# BMS_AFE_-_Cell_Inputs.net
KiCad netlist of a schematic drawn in Altium Designer
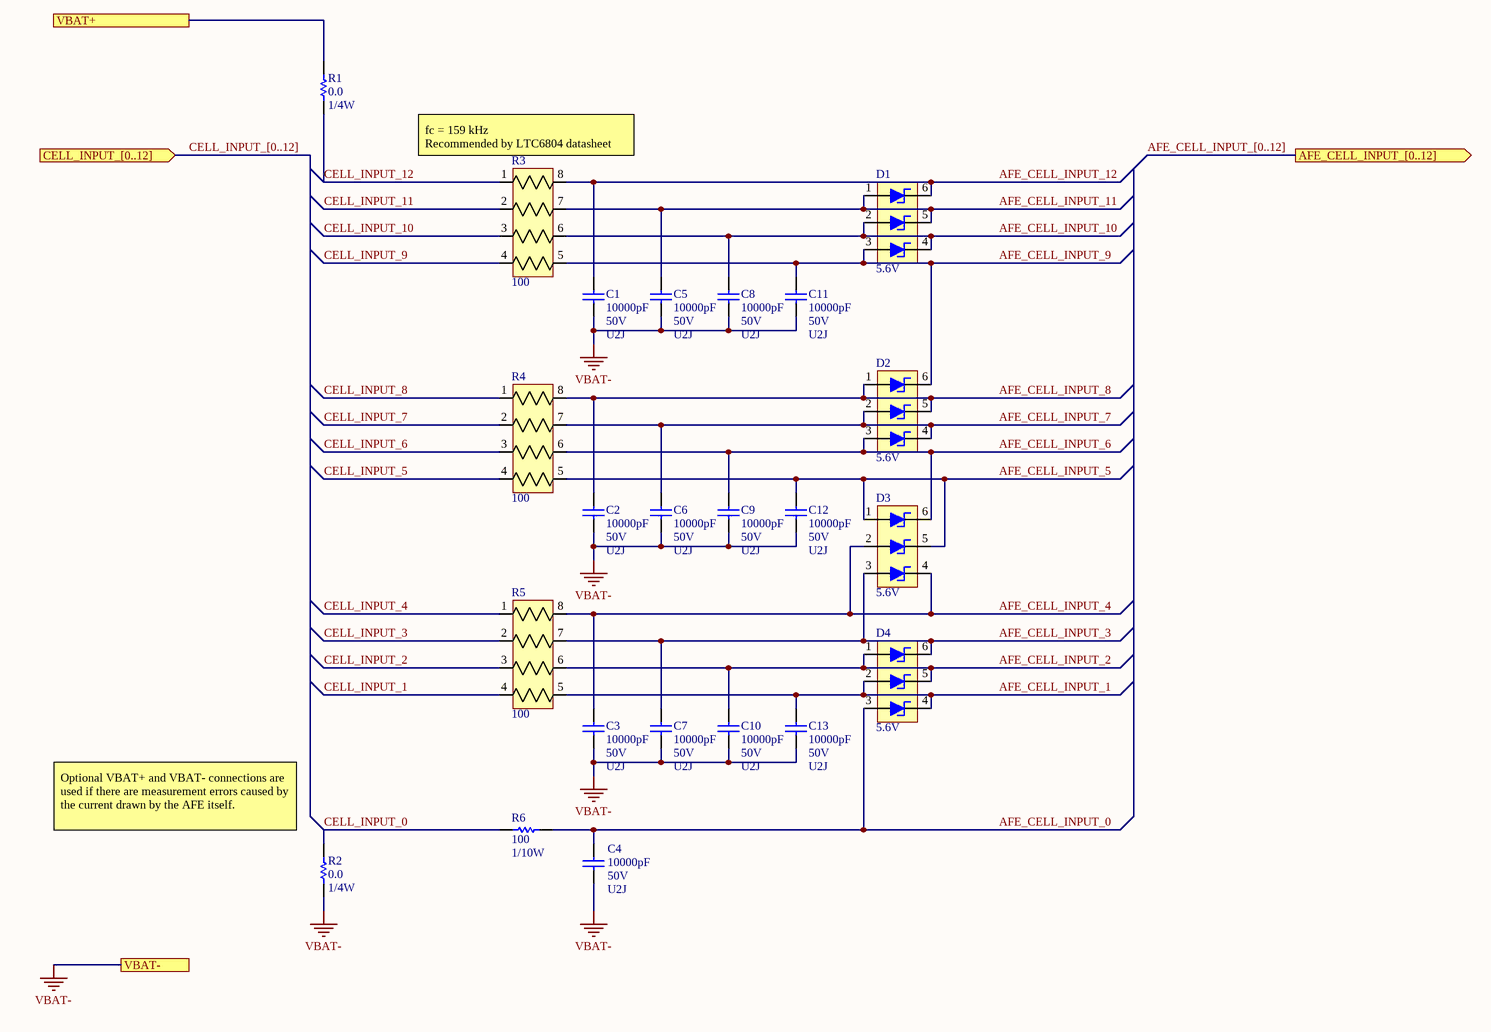
[diagram p0: BMS AFE - Cell Inputs.SchDoc]

(export (version "E")
  (design (tool "Eeschema 10.0.6"))
  (components
    (comp (ref "C1")
      (value "CAP CER 10nF 50V 5% X7R 0603")
      (footprint "CAP, 0603")
      (description "10000pF ±5% 50V Ceramic Capacitor U2J 0603 (1608 Metric)")
      (fields
        (field (name "TOLERANCE") "±5%")
        (field (name "CAPACITANCE") "10000pF")
        (field (name "VOLTAGE") "50V")
        (field (name "TEMPERATURE COEFFICIENT") "U2J")
      )
      (libsource (lib "Schematic Diagrams") (part "CAP CER 10nF 50V 5% X7R 0603"))
    )
    (comp (ref "C2")
      (value "CAP CER 10nF 50V 5% X7R 0603")
      (footprint "CAP, 0603")
      (description "10000pF ±5% 50V Ceramic Capacitor U2J 0603 (1608 Metric)")
      (fields
        (field (name "TOLERANCE") "±5%")
        (field (name "CAPACITANCE") "10000pF")
        (field (name "VOLTAGE") "50V")
        (field (name "TEMPERATURE COEFFICIENT") "U2J")
      )
      (libsource (lib "Schematic Diagrams") (part "CAP CER 10nF 50V 5% X7R 0603"))
    )
    (comp (ref "C3")
      (value "CAP CER 10nF 50V 5% X7R 0603")
      (footprint "CAP, 0603")
      (description "10000pF ±5% 50V Ceramic Capacitor U2J 0603 (1608 Metric)")
      (fields
        (field (name "TOLERANCE") "±5%")
        (field (name "CAPACITANCE") "10000pF")
        (field (name "VOLTAGE") "50V")
        (field (name "TEMPERATURE COEFFICIENT") "U2J")
      )
      (libsource (lib "Schematic Diagrams") (part "CAP CER 10nF 50V 5% X7R 0603"))
    )
    (comp (ref "C4")
      (value "CAP CER 10nF 50V 5% X7R 0603")
      (footprint "CAP, 0603")
      (description "10000pF ±5% 50V Ceramic Capacitor U2J 0603 (1608 Metric)")
      (fields
        (field (name "TOLERANCE") "±5%")
        (field (name "CAPACITANCE") "10000pF")
        (field (name "VOLTAGE") "50V")
        (field (name "TEMPERATURE COEFFICIENT") "U2J")
      )
      (libsource (lib "Schematic Diagrams") (part "CAP CER 10nF 50V 5% X7R 0603"))
    )
    (comp (ref "C5")
      (value "CAP CER 10nF 50V 5% X7R 0603")
      (footprint "CAP, 0603")
      (description "10000pF ±5% 50V Ceramic Capacitor U2J 0603 (1608 Metric)")
      (fields
        (field (name "TOLERANCE") "±5%")
        (field (name "CAPACITANCE") "10000pF")
        (field (name "VOLTAGE") "50V")
        (field (name "TEMPERATURE COEFFICIENT") "U2J")
      )
      (libsource (lib "Schematic Diagrams") (part "CAP CER 10nF 50V 5% X7R 0603"))
    )
    (comp (ref "C6")
      (value "CAP CER 10nF 50V 5% X7R 0603")
      (footprint "CAP, 0603")
      (description "10000pF ±5% 50V Ceramic Capacitor U2J 0603 (1608 Metric)")
      (fields
        (field (name "TOLERANCE") "±5%")
        (field (name "CAPACITANCE") "10000pF")
        (field (name "VOLTAGE") "50V")
        (field (name "TEMPERATURE COEFFICIENT") "U2J")
      )
      (libsource (lib "Schematic Diagrams") (part "CAP CER 10nF 50V 5% X7R 0603"))
    )
    (comp (ref "C7")
      (value "CAP CER 10nF 50V 5% X7R 0603")
      (footprint "CAP, 0603")
      (description "10000pF ±5% 50V Ceramic Capacitor U2J 0603 (1608 Metric)")
      (fields
        (field (name "TOLERANCE") "±5%")
        (field (name "CAPACITANCE") "10000pF")
        (field (name "VOLTAGE") "50V")
        (field (name "TEMPERATURE COEFFICIENT") "U2J")
      )
      (libsource (lib "Schematic Diagrams") (part "CAP CER 10nF 50V 5% X7R 0603"))
    )
    (comp (ref "C8")
      (value "CAP CER 10nF 50V 5% X7R 0603")
      (footprint "CAP, 0603")
      (description "10000pF ±5% 50V Ceramic Capacitor U2J 0603 (1608 Metric)")
      (fields
        (field (name "TOLERANCE") "±5%")
        (field (name "CAPACITANCE") "10000pF")
        (field (name "VOLTAGE") "50V")
        (field (name "TEMPERATURE COEFFICIENT") "U2J")
      )
      (libsource (lib "Schematic Diagrams") (part "CAP CER 10nF 50V 5% X7R 0603"))
    )
    (comp (ref "C9")
      (value "CAP CER 10nF 50V 5% X7R 0603")
      (footprint "CAP, 0603")
      (description "10000pF ±5% 50V Ceramic Capacitor U2J 0603 (1608 Metric)")
      (fields
        (field (name "TOLERANCE") "±5%")
        (field (name "CAPACITANCE") "10000pF")
        (field (name "VOLTAGE") "50V")
        (field (name "TEMPERATURE COEFFICIENT") "U2J")
      )
      (libsource (lib "Schematic Diagrams") (part "CAP CER 10nF 50V 5% X7R 0603"))
    )
    (comp (ref "C10")
      (value "CAP CER 10nF 50V 5% X7R 0603")
      (footprint "CAP, 0603")
      (description "10000pF ±5% 50V Ceramic Capacitor U2J 0603 (1608 Metric)")
      (fields
        (field (name "TOLERANCE") "±5%")
        (field (name "CAPACITANCE") "10000pF")
        (field (name "VOLTAGE") "50V")
        (field (name "TEMPERATURE COEFFICIENT") "U2J")
      )
      (libsource (lib "Schematic Diagrams") (part "CAP CER 10nF 50V 5% X7R 0603"))
    )
    (comp (ref "C11")
      (value "CAP CER 10nF 50V 5% X7R 0603")
      (footprint "CAP, 0603")
      (description "10000pF ±5% 50V Ceramic Capacitor U2J 0603 (1608 Metric)")
      (fields
        (field (name "TOLERANCE") "±5%")
        (field (name "CAPACITANCE") "10000pF")
        (field (name "VOLTAGE") "50V")
        (field (name "TEMPERATURE COEFFICIENT") "U2J")
      )
      (libsource (lib "Schematic Diagrams") (part "CAP CER 10nF 50V 5% X7R 0603"))
    )
    (comp (ref "C12")
      (value "CAP CER 10nF 50V 5% X7R 0603")
      (footprint "CAP, 0603")
      (description "10000pF ±5% 50V Ceramic Capacitor U2J 0603 (1608 Metric)")
      (fields
        (field (name "TOLERANCE") "±5%")
        (field (name "CAPACITANCE") "10000pF")
        (field (name "VOLTAGE") "50V")
        (field (name "TEMPERATURE COEFFICIENT") "U2J")
      )
      (libsource (lib "Schematic Diagrams") (part "CAP CER 10nF 50V 5% X7R 0603"))
    )
    (comp (ref "C13")
      (value "CAP CER 10nF 50V 5% X7R 0603")
      (footprint "CAP, 0603")
      (description "10000pF ±5% 50V Ceramic Capacitor U2J 0603 (1608 Metric)")
      (fields
        (field (name "TOLERANCE") "±5%")
        (field (name "CAPACITANCE") "10000pF")
        (field (name "VOLTAGE") "50V")
        (field (name "TEMPERATURE COEFFICIENT") "U2J")
      )
      (libsource (lib "Schematic Diagrams") (part "CAP CER 10nF 50V 5% X7R 0603"))
    )
    (comp (ref "D1")
      (value "5.6V")
      (footprint "SOT-363")
      (description "Zener Diode Array 3 Independent 5.6V 200mW ±6% SOT-363")
      (fields (field (name "TOLERANCE") "6%") (field (name "MANUFACTURER") "Diodes"))
      (libsource (lib "Schematic Diagrams") (part "DIODE ZENER ARRAY 5.6V SOT363"))
    )
    (comp (ref "D2")
      (value "5.6V")
      (footprint "SOT-363")
      (description "Zener Diode Array 3 Independent 5.6V 200mW ±6% SOT-363")
      (fields (field (name "TOLERANCE") "6%") (field (name "MANUFACTURER") "Diodes"))
      (libsource (lib "Schematic Diagrams") (part "DIODE ZENER ARRAY 5.6V SOT363"))
    )
    (comp (ref "D3")
      (value "5.6V")
      (footprint "SOT-363")
      (description "Zener Diode Array 3 Independent 5.6V 200mW ±6% SOT-363")
      (fields (field (name "TOLERANCE") "6%") (field (name "MANUFACTURER") "Diodes"))
      (libsource (lib "Schematic Diagrams") (part "DIODE ZENER ARRAY 5.6V SOT363"))
    )
    (comp (ref "D4")
      (value "5.6V")
      (footprint "SOT-363")
      (description "Zener Diode Array 3 Independent 5.6V 200mW ±6% SOT-363")
      (fields (field (name "TOLERANCE") "6%") (field (name "MANUFACTURER") "Diodes"))
      (libsource (lib "Schematic Diagrams") (part "DIODE ZENER ARRAY 5.6V SOT363"))
    )
    (comp (ref "R1")
      (value "RES 0.0 OHM 1/4W 0603")
      (footprint "RES, 0603")
      (description "RES SMD 0.0 OHM JUMPER 1/4W 0603")
      (fields (field (name "RESISTANCE") "0.0") (field (name "POWER (WATTS)") "1/4W"))
      (libsource (lib "Schematic Diagrams") (part "RES 0.0 OHM 1/4W 0603"))
    )
    (comp (ref "R2")
      (value "RES 0.0 OHM 1/4W 0603")
      (footprint "RES, 0603")
      (description "RES SMD 0.0 OHM JUMPER 1/4W 0603")
      (fields (field (name "RESISTANCE") "0.0") (field (name "POWER (WATTS)") "1/4W"))
      (libsource (lib "Schematic Diagrams") (part "RES 0.0 OHM 1/4W 0603"))
    )
    (comp (ref "R3")
      (value "RES ARRAY 100 OHM 0.5% 4RES 1206")
      (footprint "RES ARRAY 4RES 1206")
      (fields
        (field (name "MANUFACTURER") "Vishay Beyschlag")
        (field (name "MANUFACTURER PART NUMBER") "ACASA1002S1002P100")
        (field (name "TOLERANCE") "±0.5%")
        (field (name "RESISTANCE") "100")
      )
      (libsource (lib "Schematic Diagrams") (part "RES ARRAY 100 OHM 0.5% 4RES 1206"))
    )
    (comp (ref "R4")
      (value "RES ARRAY 100 OHM 0.5% 4RES 1206")
      (footprint "RES ARRAY 4RES 1206")
      (fields
        (field (name "MANUFACTURER") "Vishay Beyschlag")
        (field (name "MANUFACTURER PART NUMBER") "ACASA1002S1002P100")
        (field (name "TOLERANCE") "±0.5%")
        (field (name "RESISTANCE") "100")
      )
      (libsource (lib "Schematic Diagrams") (part "RES ARRAY 100 OHM 0.5% 4RES 1206"))
    )
    (comp (ref "R5")
      (value "RES ARRAY 100 OHM 0.5% 4RES 1206")
      (footprint "RES ARRAY 4RES 1206")
      (fields
        (field (name "MANUFACTURER") "Vishay Beyschlag")
        (field (name "MANUFACTURER PART NUMBER") "ACASA1002S1002P100")
        (field (name "TOLERANCE") "±0.5%")
        (field (name "RESISTANCE") "100")
      )
      (libsource (lib "Schematic Diagrams") (part "RES ARRAY 100 OHM 0.5% 4RES 1206"))
    )
    (comp (ref "R6")
      (value "RES 100 OHM 1% 1/10W 0603")
      (footprint "RES, 0603")
      (description "100 Ohm ±1% 0.1W, 1/10W Chip Resistor 0603 (1608 Metric) Moisture Resistant Thick Film")
      (fields
        (field (name "TOLERANCE") "±1%")
        (field (name "RESISTANCE") "100")
        (field (name "POWER") "1/10W")
      )
      (libsource (lib "Schematic Diagrams") (part "RES 100 OHM 1% 1/10W 0603"))
    )
  )
  (nets
    (net (code "1") (name "/AFE_CELL_INPUT_0") (class "Default")
      (node (ref "C4") (pin "1") (pinfunction "1_1") (pintype "passive"))
      (node (ref "D4") (pin "3") (pinfunction "A3_3") (pintype "passive"))
      (node (ref "R6") (pin "2") (pinfunction "2_2") (pintype "passive"))
    )
    (net (code "2") (name "/AFE_CELL_INPUT_1") (class "Default")
      (node (ref "C13") (pin "1") (pinfunction "1_1") (pintype "passive"))
      (node (ref "D4") (pin "2") (pinfunction "A2_2") (pintype "passive"))
      (node (ref "D4") (pin "4") (pinfunction "C3_4") (pintype "passive"))
      (node (ref "R5") (pin "5") (pinfunction "5_5") (pintype "passive"))
    )
    (net (code "3") (name "/AFE_CELL_INPUT_2") (class "Default")
      (node (ref "C10") (pin "1") (pinfunction "1_1") (pintype "passive"))
      (node (ref "D4") (pin "1") (pinfunction "A1_1") (pintype "passive"))
      (node (ref "D4") (pin "5") (pinfunction "C2_5") (pintype "passive"))
      (node (ref "R5") (pin "6") (pinfunction "6_6") (pintype "passive"))
    )
    (net (code "4") (name "/AFE_CELL_INPUT_3") (class "Default")
      (node (ref "C7") (pin "1") (pinfunction "1_1") (pintype "passive"))
      (node (ref "D3") (pin "3") (pinfunction "A3_3") (pintype "passive"))
      (node (ref "D4") (pin "6") (pinfunction "C1_6") (pintype "passive"))
      (node (ref "R5") (pin "7") (pinfunction "7_7") (pintype "passive"))
    )
    (net (code "5") (name "/AFE_CELL_INPUT_4") (class "Default")
      (node (ref "C3") (pin "1") (pinfunction "1_1") (pintype "passive"))
      (node (ref "D3") (pin "2") (pinfunction "A2_2") (pintype "passive"))
      (node (ref "D3") (pin "4") (pinfunction "C3_4") (pintype "passive"))
      (node (ref "R5") (pin "8") (pinfunction "8_8") (pintype "passive"))
    )
    (net (code "6") (name "/AFE_CELL_INPUT_5") (class "Default")
      (node (ref "C12") (pin "1") (pinfunction "1_1") (pintype "passive"))
      (node (ref "D3") (pin "1") (pinfunction "A1_1") (pintype "passive"))
      (node (ref "D3") (pin "5") (pinfunction "C2_5") (pintype "passive"))
      (node (ref "R4") (pin "5") (pinfunction "5_5") (pintype "passive"))
    )
    (net (code "7") (name "/AFE_CELL_INPUT_6") (class "Default")
      (node (ref "C9") (pin "1") (pinfunction "1_1") (pintype "passive"))
      (node (ref "D2") (pin "3") (pinfunction "A3_3") (pintype "passive"))
      (node (ref "D3") (pin "6") (pinfunction "C1_6") (pintype "passive"))
      (node (ref "R4") (pin "6") (pinfunction "6_6") (pintype "passive"))
    )
    (net (code "8") (name "/AFE_CELL_INPUT_7") (class "Default")
      (node (ref "C6") (pin "1") (pinfunction "1_1") (pintype "passive"))
      (node (ref "D2") (pin "2") (pinfunction "A2_2") (pintype "passive"))
      (node (ref "D2") (pin "4") (pinfunction "C3_4") (pintype "passive"))
      (node (ref "R4") (pin "7") (pinfunction "7_7") (pintype "passive"))
    )
    (net (code "9") (name "/AFE_CELL_INPUT_8") (class "Default")
      (node (ref "C2") (pin "1") (pinfunction "1_1") (pintype "passive"))
      (node (ref "D2") (pin "1") (pinfunction "A1_1") (pintype "passive"))
      (node (ref "D2") (pin "5") (pinfunction "C2_5") (pintype "passive"))
      (node (ref "R4") (pin "8") (pinfunction "8_8") (pintype "passive"))
    )
    (net (code "10") (name "/AFE_CELL_INPUT_9") (class "Default")
      (node (ref "C11") (pin "1") (pinfunction "1_1") (pintype "passive"))
      (node (ref "D1") (pin "3") (pinfunction "A3_3") (pintype "passive"))
      (node (ref "D2") (pin "6") (pinfunction "C1_6") (pintype "passive"))
      (node (ref "R3") (pin "5") (pinfunction "5_5") (pintype "passive"))
    )
    (net (code "11") (name "/AFE_CELL_INPUT_10") (class "Default")
      (node (ref "C8") (pin "1") (pinfunction "1_1") (pintype "passive"))
      (node (ref "D1") (pin "2") (pinfunction "A2_2") (pintype "passive"))
      (node (ref "D1") (pin "4") (pinfunction "C3_4") (pintype "passive"))
      (node (ref "R3") (pin "6") (pinfunction "6_6") (pintype "passive"))
    )
    (net (code "12") (name "/AFE_CELL_INPUT_11") (class "Default")
      (node (ref "C5") (pin "1") (pinfunction "1_1") (pintype "passive"))
      (node (ref "D1") (pin "1") (pinfunction "A1_1") (pintype "passive"))
      (node (ref "D1") (pin "5") (pinfunction "C2_5") (pintype "passive"))
      (node (ref "R3") (pin "7") (pinfunction "7_7") (pintype "passive"))
    )
    (net (code "13") (name "/AFE_CELL_INPUT_12") (class "Default")
      (node (ref "C1") (pin "1") (pinfunction "1_1") (pintype "passive"))
      (node (ref "D1") (pin "6") (pinfunction "C1_6") (pintype "passive"))
      (node (ref "R3") (pin "8") (pinfunction "8_8") (pintype "passive"))
    )
    (net (code "15") (name "/CELL_INPUT_0") (class "Default")
      (node (ref "R2") (pin "1") (pinfunction "1_1") (pintype "passive"))
      (node (ref "R6") (pin "1") (pinfunction "1_1") (pintype "passive"))
    )
    (net (code "16") (name "/CELL_INPUT_1") (class "Default")
      (node (ref "R5") (pin "4") (pinfunction "4_4") (pintype "passive"))
    )
    (net (code "17") (name "/CELL_INPUT_2") (class "Default")
      (node (ref "R5") (pin "3") (pinfunction "3_3") (pintype "passive"))
    )
    (net (code "18") (name "/CELL_INPUT_3") (class "Default")
      (node (ref "R5") (pin "2") (pinfunction "2_2") (pintype "passive"))
    )
    (net (code "19") (name "/CELL_INPUT_4") (class "Default")
      (node (ref "R5") (pin "1") (pinfunction "1_1") (pintype "passive"))
    )
    (net (code "20") (name "/CELL_INPUT_5") (class "Default")
      (node (ref "R4") (pin "4") (pinfunction "4_4") (pintype "passive"))
    )
    (net (code "21") (name "/CELL_INPUT_6") (class "Default")
      (node (ref "R4") (pin "3") (pinfunction "3_3") (pintype "passive"))
    )
    (net (code "22") (name "/CELL_INPUT_7") (class "Default")
      (node (ref "R4") (pin "2") (pinfunction "2_2") (pintype "passive"))
    )
    (net (code "23") (name "/CELL_INPUT_8") (class "Default")
      (node (ref "R4") (pin "1") (pinfunction "1_1") (pintype "passive"))
    )
    (net (code "24") (name "/CELL_INPUT_9") (class "Default")
      (node (ref "R3") (pin "4") (pinfunction "4_4") (pintype "passive"))
    )
    (net (code "25") (name "/CELL_INPUT_10") (class "Default")
      (node (ref "R3") (pin "3") (pinfunction "3_3") (pintype "passive"))
    )
    (net (code "26") (name "/CELL_INPUT_11") (class "Default")
      (node (ref "R3") (pin "2") (pinfunction "2_2") (pintype "passive"))
    )
    (net (code "27") (name "/CELL_INPUT_12") (class "Default")
      (node (ref "R1") (pin "2") (pinfunction "2_2") (pintype "passive"))
      (node (ref "R3") (pin "1") (pinfunction "1_1") (pintype "passive"))
    )
    (net (code "29") (name "/VBAT+") (class "Default")
      (node (ref "R1") (pin "1") (pinfunction "1_1") (pintype "passive"))
    )
    (net (code "30") (name "VBAT-") (class "Default")
      (node (ref "C1") (pin "2") (pinfunction "2_2") (pintype "passive"))
      (node (ref "C10") (pin "2") (pinfunction "2_2") (pintype "passive"))
      (node (ref "C11") (pin "2") (pinfunction "2_2") (pintype "passive"))
      (node (ref "C12") (pin "2") (pinfunction "2_2") (pintype "passive"))
      (node (ref "C13") (pin "2") (pinfunction "2_2") (pintype "passive"))
      (node (ref "C2") (pin "2") (pinfunction "2_2") (pintype "passive"))
      (node (ref "C3") (pin "2") (pinfunction "2_2") (pintype "passive"))
      (node (ref "C4") (pin "2") (pinfunction "2_2") (pintype "passive"))
      (node (ref "C5") (pin "2") (pinfunction "2_2") (pintype "passive"))
      (node (ref "C6") (pin "2") (pinfunction "2_2") (pintype "passive"))
      (node (ref "C7") (pin "2") (pinfunction "2_2") (pintype "passive"))
      (node (ref "C8") (pin "2") (pinfunction "2_2") (pintype "passive"))
      (node (ref "C9") (pin "2") (pinfunction "2_2") (pintype "passive"))
      (node (ref "R2") (pin "2") (pinfunction "2_2") (pintype "passive"))
    )
  )
)
